# 23-LoadCell.net
KiCad netlist of a schematic drawn in Altium Designer
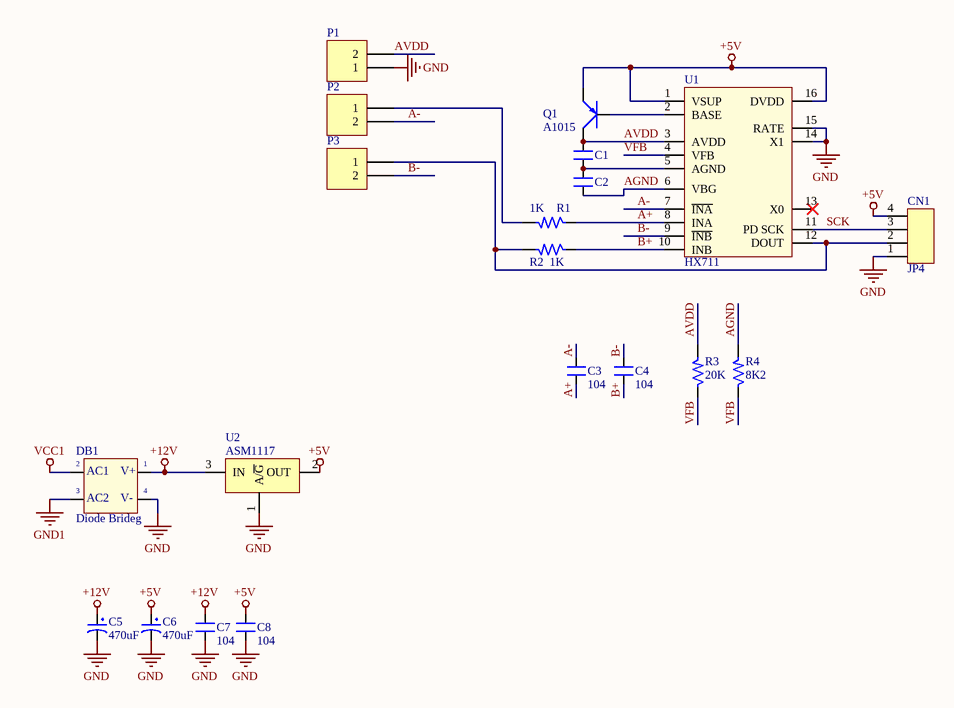
[diagram p0: 23-LoadCell.SchDoc]

(export (version "E")
  (design (tool "Eeschema 10.0.6"))
  (components
    (comp (ref "C1")
      (value "106")
      (footprint "C-0805")
      (fields (field (name "DESIGNED BY") "VanDungEvn"))
      (libsource (lib "syhaunguyen") (part "CN"))
    )
    (comp (ref "C2")
      (value "106")
      (footprint "C-0805")
      (fields (field (name "DESIGNED BY") "VanDungEvn"))
      (libsource (lib "syhaunguyen") (part "CN"))
    )
    (comp (ref "C3")
      (value "104")
      (footprint "C-0805")
      (fields (field (name "DESIGNED BY") "VanDungEvn"))
      (libsource (lib "syhaunguyen") (part "CN"))
    )
    (comp (ref "C4")
      (value "104")
      (footprint "C-0805")
      (fields (field (name "DESIGNED BY") "VanDungEvn"))
      (libsource (lib "syhaunguyen") (part "CN"))
    )
    (comp (ref "C5")
      (value "470uF")
      (footprint "C-ALU-D6.5")
      (description "Cap P  0,1uF < 22uF , 16 - 50V")
      (libsource (lib "PART") (part "CP1"))
    )
    (comp (ref "C6")
      (value "470uF")
      (footprint "C-ALU-D6.5")
      (description "Cap P  0,1uF < 22uF , 16 - 50V")
      (libsource (lib "PART") (part "CP1"))
    )
    (comp (ref "C7")
      (value "104")
      (footprint "C-0805")
      (fields (field (name "DESIGNED BY") "VanDungEvn"))
      (libsource (lib "syhaunguyen") (part "CN"))
    )
    (comp (ref "C8")
      (value "104")
      (footprint "C-0805")
      (fields (field (name "DESIGNED BY") "VanDungEvn"))
      (libsource (lib "syhaunguyen") (part "CN"))
    )
    (comp (ref "CN1") (value "JP4") (footprint "JP4") (libsource (lib "doAnTotNghiep2017Lib") (part "JP4")))
    (comp (ref "DB1")
      (value "Diode Brideg")
      (footprint "D-DB-1A-SMD")
      (description "Convert AC to DC voltage, 4 pin")
      (libsource (lib "PART") (part "DB"))
    )
    (comp (ref "P1")
      (value "KF301-2P")
      (footprint "TER-KF301-2")
      (description "Header, 2-Pin")
      (fields (field (name "PUBLISHER") "Altium Limited"))
      (libsource (lib "") (part "Header 2_1"))
    )
    (comp (ref "P2")
      (value "KF301-2P")
      (footprint "TER-KF301-2")
      (description "Header, 2-Pin")
      (fields (field (name "PUBLISHER") "Altium Limited"))
      (libsource (lib "Miscellaneous Connectors") (part "Header 2"))
    )
    (comp (ref "P3")
      (value "KF301-2P")
      (footprint "TER-KF301-2")
      (description "Header, 2-Pin")
      (fields (field (name "PUBLISHER") "Altium Limited"))
      (libsource (lib "Miscellaneous Connectors") (part "Header 2"))
    )
    (comp (ref "Q1")
      (value "A1015")
      (footprint "SOT-23-3")
      (description "PNP 600mW, ECB")
      (libsource (lib "PART") (part "A1015"))
    )
    (comp (ref "R1")
      (value "1K")
      (footprint "R-0805")
      (description "Resistor 1/4W")
      (libsource (lib "PART") (part "R"))
    )
    (comp (ref "R2")
      (value "1K")
      (footprint "R-0805")
      (description "Resistor 1/4W")
      (libsource (lib "PART") (part "R"))
    )
    (comp (ref "R3")
      (value "20K")
      (footprint "R-0805")
      (description "Resistor 1/4W")
      (libsource (lib "PART") (part "R"))
    )
    (comp (ref "R4")
      (value "8K2")
      (footprint "R-0805")
      (description "Resistor 1/4W")
      (libsource (lib "PART") (part "R"))
    )
    (comp (ref "U1")
      (value "HX711")
      (footprint "SOP-16L")
      (libsource (lib "doAnTotNghiep2017Lib") (part "HX711"))
    )
    (comp (ref "U2")
      (value "ASM1117")
      (footprint "TO-252")
      (libsource (lib "doAnTotNghiep2017Lib") (part "ASM1117"))
    )
  )
  (nets
    (net (code "1") (name "+5V") (class "Default")
      (node (ref "C6") (pin "1") (pinfunction "1_1") (pintype "passive"))
      (node (ref "C8") (pin "2") (pinfunction "2_2") (pintype "passive"))
      (node (ref "CN1") (pin "4") (pintype "passive"))
      (node (ref "Q1") (pin "1") (pinfunction "E_1") (pintype "passive"))
      (node (ref "U1") (pin "1") (pinfunction "VSUP_1") (pintype "passive"))
      (node (ref "U1") (pin "16") (pinfunction "DVDD_16") (pintype "passive"))
      (node (ref "U2") (pin "2") (pinfunction "OUT_2") (pintype "passive"))
    )
    (net (code "2") (name "+12V") (class "Default")
      (node (ref "C5") (pin "1") (pinfunction "1_1") (pintype "passive"))
      (node (ref "C7") (pin "2") (pinfunction "2_2") (pintype "passive"))
      (node (ref "DB1") (pin "3") (pinfunction "AC2_3") (pintype "passive"))
      (node (ref "U2") (pin "3") (pinfunction "IN_3") (pintype "passive"))
    )
    (net (code "3") (name "/A+") (class "Default")
      (node (ref "C3") (pin "1") (pinfunction "1_1") (pintype "passive"))
      (node (ref "R1") (pin "1") (pinfunction "1_1") (pintype "passive"))
      (node (ref "U1") (pin "8") (pinfunction "INA_8") (pintype "passive"))
    )
    (net (code "4") (name "/A-") (class "Default")
      (node (ref "C3") (pin "2") (pinfunction "2_2") (pintype "passive"))
      (node (ref "P2") (pin "2") (pinfunction "2_2") (pintype "passive"))
      (node (ref "U1") (pin "7") (pinfunction "~{INA}_7") (pintype "passive"))
    )
    (net (code "5") (name "/AGND") (class "Default")
      (node (ref "C2") (pin "1") (pinfunction "1_1") (pintype "passive"))
      (node (ref "R4") (pin "2") (pinfunction "2_2") (pintype "passive"))
      (node (ref "U1") (pin "6") (pinfunction "VBG_6") (pintype "passive"))
    )
    (net (code "6") (name "/AVDD") (class "Default")
      (node (ref "C1") (pin "2") (pinfunction "2_2") (pintype "passive"))
      (node (ref "P1") (pin "2") (pinfunction "2_2") (pintype "passive"))
      (node (ref "Q1") (pin "2") (pinfunction "C_2") (pintype "passive"))
      (node (ref "R3") (pin "2") (pinfunction "2_2") (pintype "passive"))
      (node (ref "U1") (pin "3") (pinfunction "AVDD_3") (pintype "passive"))
    )
    (net (code "7") (name "/B+") (class "Default")
      (node (ref "C4") (pin "1") (pinfunction "1_1") (pintype "passive"))
      (node (ref "R2") (pin "1") (pinfunction "1_1") (pintype "passive"))
      (node (ref "U1") (pin "10") (pinfunction "INB_10") (pintype "passive"))
    )
    (net (code "8") (name "/B-") (class "Default")
      (node (ref "C4") (pin "2") (pinfunction "2_2") (pintype "passive"))
      (node (ref "P3") (pin "2") (pinfunction "2_2") (pintype "passive"))
      (node (ref "U1") (pin "9") (pinfunction "~{INB}_9") (pintype "passive"))
    )
    (net (code "9") (name "/SCK") (class "Default")
      (node (ref "CN1") (pin "3") (pintype "passive"))
      (node (ref "U1") (pin "11") (pinfunction "PD_SCK_11") (pintype "passive"))
    )
    (net (code "10") (name "/VFB") (class "Default")
      (node (ref "R3") (pin "1") (pinfunction "1_1") (pintype "passive"))
      (node (ref "R4") (pin "1") (pinfunction "1_1") (pintype "passive"))
      (node (ref "U1") (pin "4") (pinfunction "VFB_4") (pintype "passive"))
    )
    (net (code "11") (name "GND") (class "Default")
      (node (ref "C5") (pin "2") (pinfunction "2_2") (pintype "passive"))
      (node (ref "C6") (pin "2") (pinfunction "2_2") (pintype "passive"))
      (node (ref "C7") (pin "1") (pinfunction "1_1") (pintype "passive"))
      (node (ref "C8") (pin "1") (pinfunction "1_1") (pintype "passive"))
      (node (ref "CN1") (pin "1") (pintype "passive"))
      (node (ref "DB1") (pin "4") (pinfunction "-V_OUT_4") (pintype "passive"))
      (node (ref "P1") (pin "1") (pinfunction "1_1") (pintype "passive"))
      (node (ref "U1") (pin "14") (pinfunction "X1_14") (pintype "passive"))
      (node (ref "U1") (pin "15") (pinfunction "RATE_15") (pintype "passive"))
      (node (ref "U2") (pin "1") (pinfunction "A/~{G}_1") (pintype "passive"))
    )
    (net (code "12") (name "GND1") (class "Default")
      (node (ref "DB1") (pin "1") (pinfunction "+V_OUT_1") (pintype "passive"))
    )
    (net (code "13") (name "Net-(P2-Pad1)") (class "Default")
      (node (ref "P2") (pin "1") (pinfunction "1_1") (pintype "passive"))
      (node (ref "R1") (pin "2") (pinfunction "2_2") (pintype "passive"))
    )
    (net (code "14") (name "Net-(Q1-B)") (class "Default")
      (node (ref "Q1") (pin "3") (pinfunction "B_3") (pintype "passive"))
      (node (ref "U1") (pin "2") (pinfunction "BASE_2") (pintype "passive"))
    )
    (net (code "15") (name "Net-(U1-AGND)") (class "Default")
      (node (ref "C1") (pin "1") (pinfunction "1_1") (pintype "passive"))
      (node (ref "C2") (pin "2") (pinfunction "2_2") (pintype "passive"))
      (node (ref "U1") (pin "5") (pinfunction "AGND_5") (pintype "passive"))
    )
    (net (code "16") (name "Net-(U1-DOUT)") (class "Default")
      (node (ref "CN1") (pin "2") (pintype "passive"))
      (node (ref "P3") (pin "1") (pinfunction "1_1") (pintype "passive"))
      (node (ref "R2") (pin "2") (pinfunction "2_2") (pintype "passive"))
      (node (ref "U1") (pin "12") (pinfunction "DOUT_12") (pintype "passive"))
    )
    (net (code "17") (name "VCC1") (class "Default")
      (node (ref "DB1") (pin "2") (pinfunction "AC1_2") (pintype "passive"))
    )
    (net (code "18") (name "unconnected-(U1-X0-Pad13)") (class "Default")
      (node (ref "U1") (pin "13") (pinfunction "X0_13") (pintype "passive+no_connect"))
    )
  )
)
